# Misc_IO.net
KiCad netlist of a schematic drawn in Altium Designer
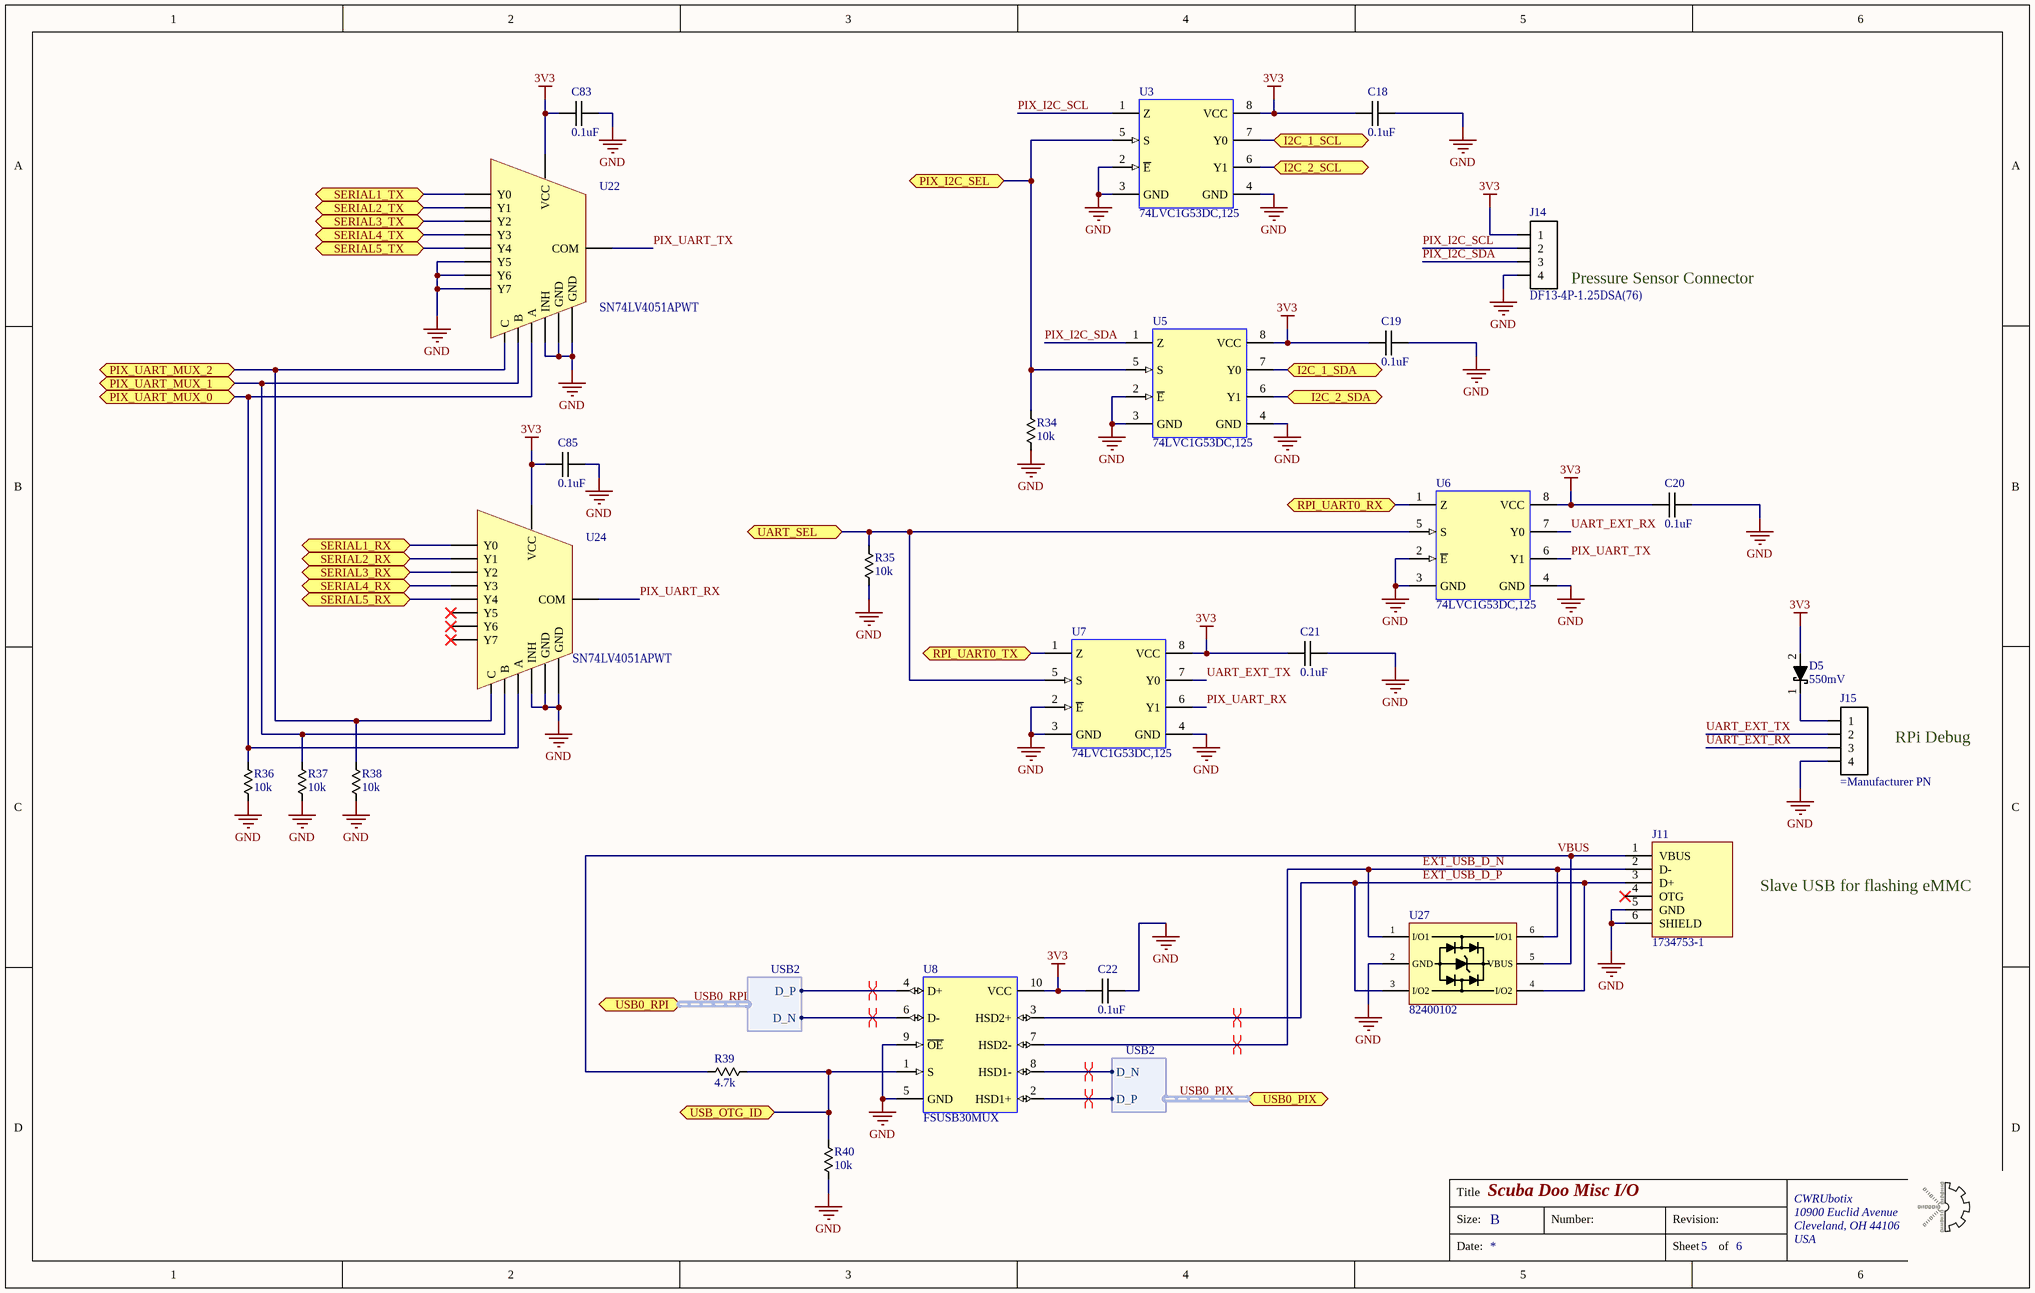
[diagram p0: Misc_IO.SchDoc]

(export (version "E")
  (design (tool "Eeschema 10.0.6"))
  (components
    (comp (ref "C18")
      (value "0.1uF")
      (footprint "chip_0603")
      (description "CAP, 0.1uF, ±10%, 16V, X7R, 0603")
      (fields (field (name "PART NUMBER") "CAP-00542") (field (name "TOLERANCE") "±10%"))
      (libsource (lib "Capacitors$") (part "CAP-00542"))
    )
    (comp (ref "C19")
      (value "0.1uF")
      (footprint "chip_0603")
      (description "CAP, 0.1uF, ±10%, 16V, X7R, 0603")
      (fields (field (name "PART NUMBER") "CAP-00542") (field (name "TOLERANCE") "±10%"))
      (libsource (lib "Capacitors$") (part "CAP-00542"))
    )
    (comp (ref "C20")
      (value "0.1uF")
      (footprint "chip_0603")
      (description "CAP, 0.1uF, ±10%, 16V, X7R, 0603")
      (fields (field (name "PART NUMBER") "CAP-00542") (field (name "TOLERANCE") "±10%"))
      (libsource (lib "Capacitors$") (part "CAP-00542"))
    )
    (comp (ref "C21")
      (value "0.1uF")
      (footprint "chip_0603")
      (description "CAP, 0.1uF, ±10%, 16V, X7R, 0603")
      (fields (field (name "PART NUMBER") "CAP-00542") (field (name "TOLERANCE") "±10%"))
      (libsource (lib "Capacitors$") (part "CAP-00542"))
    )
    (comp (ref "C22")
      (value "0.1uF")
      (footprint "chip_0603")
      (description "CAP, 0.1uF, ±10%, 16V, X7R, 0603")
      (fields (field (name "PART NUMBER") "CAP-00542") (field (name "TOLERANCE") "±10%"))
      (libsource (lib "Capacitors$") (part "CAP-00542"))
    )
    (comp (ref "C83")
      (value "0.1uF")
      (footprint "chip_0603")
      (description "CAP, 0.1uF, ±10%, 16V, X7R, 0603")
      (fields (field (name "PART NUMBER") "CAP-00542") (field (name "TOLERANCE") "±10%"))
      (libsource (lib "Capacitors$") (part "CAP-00542"))
    )
    (comp (ref "C85")
      (value "0.1uF")
      (footprint "chip_0603")
      (description "CAP, 0.1uF, ±10%, 16V, X7R, 0603")
      (fields (field (name "PART NUMBER") "CAP-00542") (field (name "TOLERANCE") "±10%"))
      (libsource (lib "Capacitors$") (part "CAP-00542"))
    )
    (comp (ref "D5")
      (value "550mV")
      (footprint "sod123_0")
      (description "Dio Shtky, 1A, 0.55V, 40V, SOD-123")
      (fields (field (name "PART NUMBER") "DIO-00001") (field (name "MANUFACTURER") "ON Semi"))
      (libsource (lib "Diodes$") (part "DIO-00001"))
    )
    (comp (ref "J11")
      (value "1734753-1")
      (footprint "TE_1734753-1")
      (description "USB Mini B Receptacle, USB 2.0, Vertical, Thru-Hole")
      (fields (field (name "PART NUMBER") "CONN-00125") (field (name "MANUFACTURER") "TE Connectivity"))
      (libsource (lib "Connectors$") (part "CONN-00125"))
    )
    (comp (ref "J14")
      (value "DF13-4P-1.25DSA(76)‎")
      (footprint "HIROSE_DF13-4P-1-25DSA")
      (description "Header, 4-Pos, Shrouded, 1.25mm Pitch, Vertical, Thru-Hole")
      (fields
        (field (name "PART NUMBER") "CONN-00118")
        (field (name "MANUFACTURER") "Hirose Electric Co Ltd")
      )
      (libsource (lib "Connectors$") (part "CONN-00118"))
    )
    (comp (ref "J15")
      (value "~")
      (footprint "HDDR_4x1_0")
      (description "Header 4x1, 0.1\"")
      (fields (field (name "PART NUMBER") "CONN-00029"))
      (libsource (lib "Connectors$") (part "CONN-00029"))
    )
    (comp (ref "R34")
      (value "10k")
      (footprint "chip_0603")
      (description "RES SMD 10K OHM 1% 1/4W 0603")
      (fields (field (name "PART NUMBER") "RES-00306") (field (name "TOLERANCE") "1%"))
      (libsource (lib "Resistors$") (part "RES-00306"))
    )
    (comp (ref "R35")
      (value "10k")
      (footprint "chip_0603")
      (description "RES SMD 10K OHM 1% 1/4W 0603")
      (fields (field (name "PART NUMBER") "RES-00306") (field (name "TOLERANCE") "1%"))
      (libsource (lib "Resistors$") (part "RES-00306"))
    )
    (comp (ref "R36")
      (value "10k")
      (footprint "chip_0603")
      (description "RES SMD 10K OHM 1% 1/4W 0603")
      (fields (field (name "PART NUMBER") "RES-00306") (field (name "TOLERANCE") "1%"))
      (libsource (lib "Resistors$") (part "RES-00306"))
    )
    (comp (ref "R37")
      (value "10k")
      (footprint "chip_0603")
      (description "RES SMD 10K OHM 1% 1/4W 0603")
      (fields (field (name "PART NUMBER") "RES-00306") (field (name "TOLERANCE") "1%"))
      (libsource (lib "Resistors$") (part "RES-00306"))
    )
    (comp (ref "R38")
      (value "10k")
      (footprint "chip_0603")
      (description "RES SMD 10K OHM 1% 1/4W 0603")
      (fields (field (name "PART NUMBER") "RES-00306") (field (name "TOLERANCE") "1%"))
      (libsource (lib "Resistors$") (part "RES-00306"))
    )
    (comp (ref "R39")
      (value "4.7k")
      (footprint "chip_0603")
      (description "RES SMD 4.7K OHM 1% 1/4W 0603")
      (fields (field (name "PART NUMBER") "RES-00470") (field (name "TOLERANCE") "1%"))
      (libsource (lib "Resistors$") (part "RES-00470"))
    )
    (comp (ref "R40")
      (value "10k")
      (footprint "chip_0603")
      (description "RES SMD 10K OHM 1% 1/4W 0603")
      (fields (field (name "PART NUMBER") "RES-00306") (field (name "TOLERANCE") "1%"))
      (libsource (lib "Resistors$") (part "RES-00306"))
    )
    (comp (ref "U3")
      (value "74LVC1G53DC,125")
      (footprint "VSSOP-8_2x2.3_P0.5mm")
      (description "IC, Analog Mux/Demux 2:1, 8-VSSOP")
      (fields (field (name "PART NUMBER") "LOGIC-00048") (field (name "MANUFACTURER") "Nexperia"))
      (libsource (lib "Logic$") (part "LOGIC-00048"))
    )
    (comp (ref "U5")
      (value "74LVC1G53DC,125")
      (footprint "VSSOP-8_2x2.3_P0.5mm")
      (description "IC, Analog Mux/Demux 2:1, 8-VSSOP")
      (fields (field (name "PART NUMBER") "LOGIC-00048") (field (name "MANUFACTURER") "Nexperia"))
      (libsource (lib "Logic$") (part "LOGIC-00048"))
    )
    (comp (ref "U6")
      (value "74LVC1G53DC,125")
      (footprint "VSSOP-8_2x2.3_P0.5mm")
      (description "IC, Analog Mux/Demux 2:1, 8-VSSOP")
      (fields (field (name "PART NUMBER") "LOGIC-00048") (field (name "MANUFACTURER") "Nexperia"))
      (libsource (lib "Logic$") (part "LOGIC-00048"))
    )
    (comp (ref "U7")
      (value "74LVC1G53DC,125")
      (footprint "VSSOP-8_2x2.3_P0.5mm")
      (description "IC, Analog Mux/Demux 2:1, 8-VSSOP")
      (fields (field (name "PART NUMBER") "LOGIC-00048") (field (name "MANUFACTURER") "Nexperia"))
      (libsource (lib "Logic$") (part "LOGIC-00048"))
    )
    (comp (ref "U8")
      (value "FSUSB30MUX")
      (footprint "MSOP-10")
      (description "IC, High-Speed USB 2.0 Switch, DPDT, FSUSB30, 10-MSOP")
      (fields (field (name "PART NUMBER") "IFACE-00037") (field (name "MANUFACTURER") "onsemi"))
      (libsource (lib "Interfaces$") (part "IFACE-00037"))
    )
    (comp (ref "U22")
      (value "SN74LV4051APWT‎")
      (footprint "TSSOP-16_0_1")
      (description "IC, Analog Mux/Demux, 8:1, TSSOP-16, SN74LV4051")
      (fields (field (name "PART NUMBER") "LOGIC-00018") (field (name "MANUFACTURER") "TI"))
      (libsource (lib "Logic$") (part "LOGIC-00018"))
    )
    (comp (ref "U24")
      (value "SN74LV4051APWT‎")
      (footprint "TSSOP-16_0_1")
      (description "IC, Analog Mux/Demux, 8:1, TSSOP-16, SN74LV4051")
      (fields (field (name "PART NUMBER") "LOGIC-00018") (field (name "MANUFACTURER") "TI"))
      (libsource (lib "Logic$") (part "LOGIC-00018"))
    )
    (comp (ref "U27")
      (value "82400102")
      (footprint "sot-23-6")
      (description "ESD Protec, 2-Ch, 2.5pF, 17V clamping voltage, SOT23-6")
      (fields (field (name "PART NUMBER") "DIO-00069") (field (name "MANUFACTURER") "ST"))
      (libsource (lib "Diodes$") (part "DIO-00069"))
    )
  )
  (nets
    (net (code "3") (name "/EXT_USB_D_N") (class "Default")
      (node (ref "J11") (pin "2") (pinfunction "D-_2") (pintype "passive"))
      (node (ref "U27") (pin "1") (pinfunction "I/O1_1") (pintype "passive"))
      (node (ref "U27") (pin "6") (pinfunction "I/O1_6") (pintype "passive"))
      (node (ref "U8") (pin "7") (pinfunction "HSD2-_7") (pintype "bidirectional"))
    )
    (net (code "4") (name "/EXT_USB_D_P") (class "Default")
      (node (ref "J11") (pin "3") (pinfunction "D+_3") (pintype "passive"))
      (node (ref "U27") (pin "3") (pinfunction "I/O2_3") (pintype "passive"))
      (node (ref "U27") (pin "4") (pinfunction "I/O2_4") (pintype "passive"))
      (node (ref "U8") (pin "3") (pinfunction "HSD2+_3") (pintype "bidirectional"))
    )
    (net (code "5") (name "/I2C_1_SCL") (class "Default")
      (node (ref "U3") (pin "7") (pinfunction "Y0_7") (pintype "passive"))
    )
    (net (code "6") (name "/I2C_1_SDA") (class "Default")
      (node (ref "U5") (pin "7") (pinfunction "Y0_7") (pintype "passive"))
    )
    (net (code "7") (name "/I2C_2_SCL") (class "Default")
      (node (ref "U3") (pin "6") (pinfunction "Y1_6") (pintype "passive"))
    )
    (net (code "8") (name "/I2C_2_SDA") (class "Default")
      (node (ref "U5") (pin "6") (pinfunction "Y1_6") (pintype "passive"))
    )
    (net (code "9") (name "/PIX_I2C_SCL") (class "Default")
      (node (ref "J14") (pin "2") (pinfunction "2_2") (pintype "passive"))
      (node (ref "U3") (pin "1") (pinfunction "Z_1") (pintype "passive"))
    )
    (net (code "10") (name "/PIX_I2C_SDA") (class "Default")
      (node (ref "J14") (pin "3") (pinfunction "3_3") (pintype "passive"))
      (node (ref "U5") (pin "1") (pinfunction "Z_1") (pintype "passive"))
    )
    (net (code "11") (name "/PIX_I2C_SEL") (class "Default")
      (node (ref "R34") (pin "1") (pinfunction "1_1") (pintype "passive"))
      (node (ref "U3") (pin "5") (pinfunction "S_5") (pintype "input"))
      (node (ref "U5") (pin "5") (pinfunction "S_5") (pintype "input"))
    )
    (net (code "12") (name "/PIX_UART_MUX_0") (class "Default")
      (node (ref "R36") (pin "1") (pinfunction "1_1") (pintype "passive"))
      (node (ref "U22") (pin "11") (pinfunction "A_11") (pintype "passive"))
      (node (ref "U24") (pin "11") (pinfunction "A_11") (pintype "passive"))
    )
    (net (code "13") (name "/PIX_UART_MUX_1") (class "Default")
      (node (ref "R37") (pin "1") (pinfunction "1_1") (pintype "passive"))
      (node (ref "U22") (pin "10") (pinfunction "B_10") (pintype "passive"))
      (node (ref "U24") (pin "10") (pinfunction "B_10") (pintype "passive"))
    )
    (net (code "14") (name "/PIX_UART_MUX_2") (class "Default")
      (node (ref "R38") (pin "1") (pinfunction "1_1") (pintype "passive"))
      (node (ref "U22") (pin "9") (pinfunction "C_9") (pintype "passive"))
      (node (ref "U24") (pin "9") (pinfunction "C_9") (pintype "passive"))
    )
    (net (code "15") (name "/PIX_UART_RX") (class "Default")
      (node (ref "U24") (pin "3") (pinfunction "COM_3") (pintype "passive"))
      (node (ref "U7") (pin "6") (pinfunction "Y1_6") (pintype "passive"))
    )
    (net (code "16") (name "/PIX_UART_TX") (class "Default")
      (node (ref "U22") (pin "3") (pinfunction "COM_3") (pintype "passive"))
      (node (ref "U6") (pin "6") (pinfunction "Y1_6") (pintype "passive"))
    )
    (net (code "17") (name "/RPI_UART0_RX") (class "Default")
      (node (ref "U6") (pin "1") (pinfunction "Z_1") (pintype "passive"))
    )
    (net (code "18") (name "/RPI_UART0_TX") (class "Default")
      (node (ref "U7") (pin "1") (pinfunction "Z_1") (pintype "passive"))
    )
    (net (code "19") (name "/SERIAL1_RX") (class "Default")
      (node (ref "U24") (pin "13") (pinfunction "Y0_13") (pintype "passive"))
    )
    (net (code "20") (name "/SERIAL1_TX") (class "Default")
      (node (ref "U22") (pin "13") (pinfunction "Y0_13") (pintype "passive"))
    )
    (net (code "21") (name "/SERIAL2_RX") (class "Default")
      (node (ref "U24") (pin "14") (pinfunction "Y1_14") (pintype "passive"))
    )
    (net (code "22") (name "/SERIAL2_TX") (class "Default")
      (node (ref "U22") (pin "14") (pinfunction "Y1_14") (pintype "passive"))
    )
    (net (code "23") (name "/SERIAL3_RX") (class "Default")
      (node (ref "U24") (pin "15") (pinfunction "Y2_15") (pintype "passive"))
    )
    (net (code "24") (name "/SERIAL3_TX") (class "Default")
      (node (ref "U22") (pin "15") (pinfunction "Y2_15") (pintype "passive"))
    )
    (net (code "25") (name "/SERIAL4_RX") (class "Default")
      (node (ref "U24") (pin "12") (pinfunction "Y3_12") (pintype "passive"))
    )
    (net (code "26") (name "/SERIAL4_TX") (class "Default")
      (node (ref "U22") (pin "12") (pinfunction "Y3_12") (pintype "passive"))
    )
    (net (code "27") (name "/SERIAL5_RX") (class "Default")
      (node (ref "U24") (pin "1") (pinfunction "Y4_1") (pintype "passive"))
    )
    (net (code "28") (name "/SERIAL5_TX") (class "Default")
      (node (ref "U22") (pin "1") (pinfunction "Y4_1") (pintype "passive"))
    )
    (net (code "29") (name "/UART_EXT_RX") (class "Default")
      (node (ref "J15") (pin "3") (pinfunction "3_3") (pintype "passive"))
      (node (ref "U6") (pin "7") (pinfunction "Y0_7") (pintype "passive"))
    )
    (net (code "30") (name "/UART_EXT_TX") (class "Default")
      (node (ref "J15") (pin "2") (pinfunction "2_2") (pintype "passive"))
      (node (ref "U7") (pin "7") (pinfunction "Y0_7") (pintype "passive"))
    )
    (net (code "31") (name "/UART_SEL") (class "Default")
      (node (ref "R35") (pin "1") (pinfunction "1_1") (pintype "passive"))
      (node (ref "U6") (pin "5") (pinfunction "S_5") (pintype "input"))
      (node (ref "U7") (pin "5") (pinfunction "S_5") (pintype "input"))
    )
    (net (code "34") (name "/USB_OTG_ID") (class "Default")
      (node (ref "R39") (pin "2") (pinfunction "2_2") (pintype "passive"))
      (node (ref "R40") (pin "1") (pinfunction "1_1") (pintype "passive"))
      (node (ref "U8") (pin "1") (pinfunction "S_1") (pintype "input"))
    )
    (net (code "35") (name "/VBUS") (class "Default")
      (node (ref "J11") (pin "1") (pinfunction "VBUS_1") (pintype "passive"))
      (node (ref "R39") (pin "1") (pinfunction "1_1") (pintype "passive"))
      (node (ref "U27") (pin "5") (pinfunction "VBUS_5") (pintype "passive"))
    )
    (net (code "36") (name "3V3") (class "Default")
      (node (ref "C18") (pin "2") (pinfunction "2_2") (pintype "passive"))
      (node (ref "C19") (pin "2") (pinfunction "2_2") (pintype "passive"))
      (node (ref "C20") (pin "2") (pinfunction "2_2") (pintype "passive"))
      (node (ref "C21") (pin "2") (pinfunction "2_2") (pintype "passive"))
      (node (ref "C22") (pin "1") (pinfunction "1_1") (pintype "passive"))
      (node (ref "C83") (pin "2") (pinfunction "2_2") (pintype "passive"))
      (node (ref "C85") (pin "2") (pinfunction "2_2") (pintype "passive"))
      (node (ref "D5") (pin "2") (pinfunction "2_2") (pintype "passive"))
      (node (ref "J14") (pin "1") (pinfunction "1_1") (pintype "passive"))
      (node (ref "U22") (pin "16") (pinfunction "VCC_16") (pintype "passive"))
      (node (ref "U24") (pin "16") (pinfunction "VCC_16") (pintype "passive"))
      (node (ref "U3") (pin "8") (pinfunction "VCC_8") (pintype "power_in"))
      (node (ref "U5") (pin "8") (pinfunction "VCC_8") (pintype "power_in"))
      (node (ref "U6") (pin "8") (pinfunction "VCC_8") (pintype "power_in"))
      (node (ref "U7") (pin "8") (pinfunction "VCC_8") (pintype "power_in"))
      (node (ref "U8") (pin "10") (pinfunction "VCC_10") (pintype "power_in"))
    )
    (net (code "37") (name "GND") (class "Default")
      (node (ref "C18") (pin "1") (pinfunction "1_1") (pintype "passive"))
      (node (ref "C19") (pin "1") (pinfunction "1_1") (pintype "passive"))
      (node (ref "C20") (pin "1") (pinfunction "1_1") (pintype "passive"))
      (node (ref "C21") (pin "1") (pinfunction "1_1") (pintype "passive"))
      (node (ref "C22") (pin "2") (pinfunction "2_2") (pintype "passive"))
      (node (ref "C83") (pin "1") (pinfunction "1_1") (pintype "passive"))
      (node (ref "C85") (pin "1") (pinfunction "1_1") (pintype "passive"))
      (node (ref "J11") (pin "5") (pinfunction "GND_5") (pintype "passive"))
      (node (ref "J11") (pin "6") (pinfunction "SHIELD_6") (pintype "passive"))
      (node (ref "J14") (pin "4") (pinfunction "4_4") (pintype "passive"))
      (node (ref "J15") (pin "4") (pinfunction "4_4") (pintype "passive"))
      (node (ref "R34") (pin "2") (pinfunction "2_2") (pintype "passive"))
      (node (ref "R35") (pin "2") (pinfunction "2_2") (pintype "passive"))
      (node (ref "R36") (pin "2") (pinfunction "2_2") (pintype "passive"))
      (node (ref "R37") (pin "2") (pinfunction "2_2") (pintype "passive"))
      (node (ref "R38") (pin "2") (pinfunction "2_2") (pintype "passive"))
      (node (ref "R40") (pin "2") (pinfunction "2_2") (pintype "passive"))
      (node (ref "U22") (pin "2") (pinfunction "Y6_2") (pintype "passive"))
      (node (ref "U22") (pin "4") (pinfunction "Y7_4") (pintype "passive"))
      (node (ref "U22") (pin "5") (pinfunction "Y5_5") (pintype "passive"))
      (node (ref "U22") (pin "6") (pinfunction "INH_6") (pintype "passive"))
      (node (ref "U22") (pin "7") (pinfunction "GND_7") (pintype "passive"))
      (node (ref "U22") (pin "8") (pinfunction "GND_8") (pintype "passive"))
      (node (ref "U24") (pin "6") (pinfunction "INH_6") (pintype "passive"))
      (node (ref "U24") (pin "7") (pinfunction "GND_7") (pintype "passive"))
      (node (ref "U24") (pin "8") (pinfunction "GND_8") (pintype "passive"))
      (node (ref "U27") (pin "2") (pinfunction "GND_2") (pintype "passive"))
      (node (ref "U3") (pin "2") (pinfunction "~{E}_2") (pintype "input"))
      (node (ref "U3") (pin "3") (pinfunction "GND_3") (pintype "power_in"))
      (node (ref "U3") (pin "4") (pinfunction "GND_4") (pintype "power_in"))
      (node (ref "U5") (pin "2") (pinfunction "~{E}_2") (pintype "input"))
      (node (ref "U5") (pin "3") (pinfunction "GND_3") (pintype "power_in"))
      (node (ref "U5") (pin "4") (pinfunction "GND_4") (pintype "power_in"))
      (node (ref "U6") (pin "2") (pinfunction "~{E}_2") (pintype "input"))
      (node (ref "U6") (pin "3") (pinfunction "GND_3") (pintype "power_in"))
      (node (ref "U6") (pin "4") (pinfunction "GND_4") (pintype "power_in"))
      (node (ref "U7") (pin "2") (pinfunction "~{E}_2") (pintype "input"))
      (node (ref "U7") (pin "3") (pinfunction "GND_3") (pintype "power_in"))
      (node (ref "U7") (pin "4") (pinfunction "GND_4") (pintype "power_in"))
      (node (ref "U8") (pin "5") (pinfunction "GND_5") (pintype "power_in"))
      (node (ref "U8") (pin "9") (pinfunction "~{OE}_9") (pintype "input"))
    )
    (net (code "38") (name "Net-(D5-Pad1)") (class "Default")
      (node (ref "D5") (pin "1") (pinfunction "1_1") (pintype "passive"))
      (node (ref "J15") (pin "1") (pinfunction "1_1") (pintype "passive"))
    )
    (net (code "39") (name "unconnected-(J11-OTG-Pad4)") (class "Default")
      (node (ref "J11") (pin "4") (pinfunction "OTG_4") (pintype "passive+no_connect"))
    )
    (net (code "40") (name "unconnected-(U8-D+-Pad4)") (class "Default")
      (node (ref "U8") (pin "4") (pinfunction "D+_4") (pintype "bidirectional"))
    )
    (net (code "41") (name "unconnected-(U8-D--Pad6)") (class "Default")
      (node (ref "U8") (pin "6") (pinfunction "D-_6") (pintype "bidirectional"))
    )
    (net (code "42") (name "unconnected-(U8-HSD1+-Pad2)") (class "Default")
      (node (ref "U8") (pin "2") (pinfunction "HSD1+_2") (pintype "bidirectional"))
    )
    (net (code "43") (name "unconnected-(U8-HSD1--Pad8)") (class "Default")
      (node (ref "U8") (pin "8") (pinfunction "HSD1-_8") (pintype "bidirectional"))
    )
    (net (code "44") (name "unconnected-(U24-Y5-Pad5)") (class "Default")
      (node (ref "U24") (pin "5") (pinfunction "Y5_5") (pintype "passive+no_connect"))
    )
    (net (code "45") (name "unconnected-(U24-Y6-Pad2)") (class "Default")
      (node (ref "U24") (pin "2") (pinfunction "Y6_2") (pintype "passive+no_connect"))
    )
    (net (code "46") (name "unconnected-(U24-Y7-Pad4)") (class "Default")
      (node (ref "U24") (pin "4") (pinfunction "Y7_4") (pintype "passive+no_connect"))
    )
  )
)
